# 4_324_039__3_2.net
KiCad netlist of a schematic drawn in Altium Designer
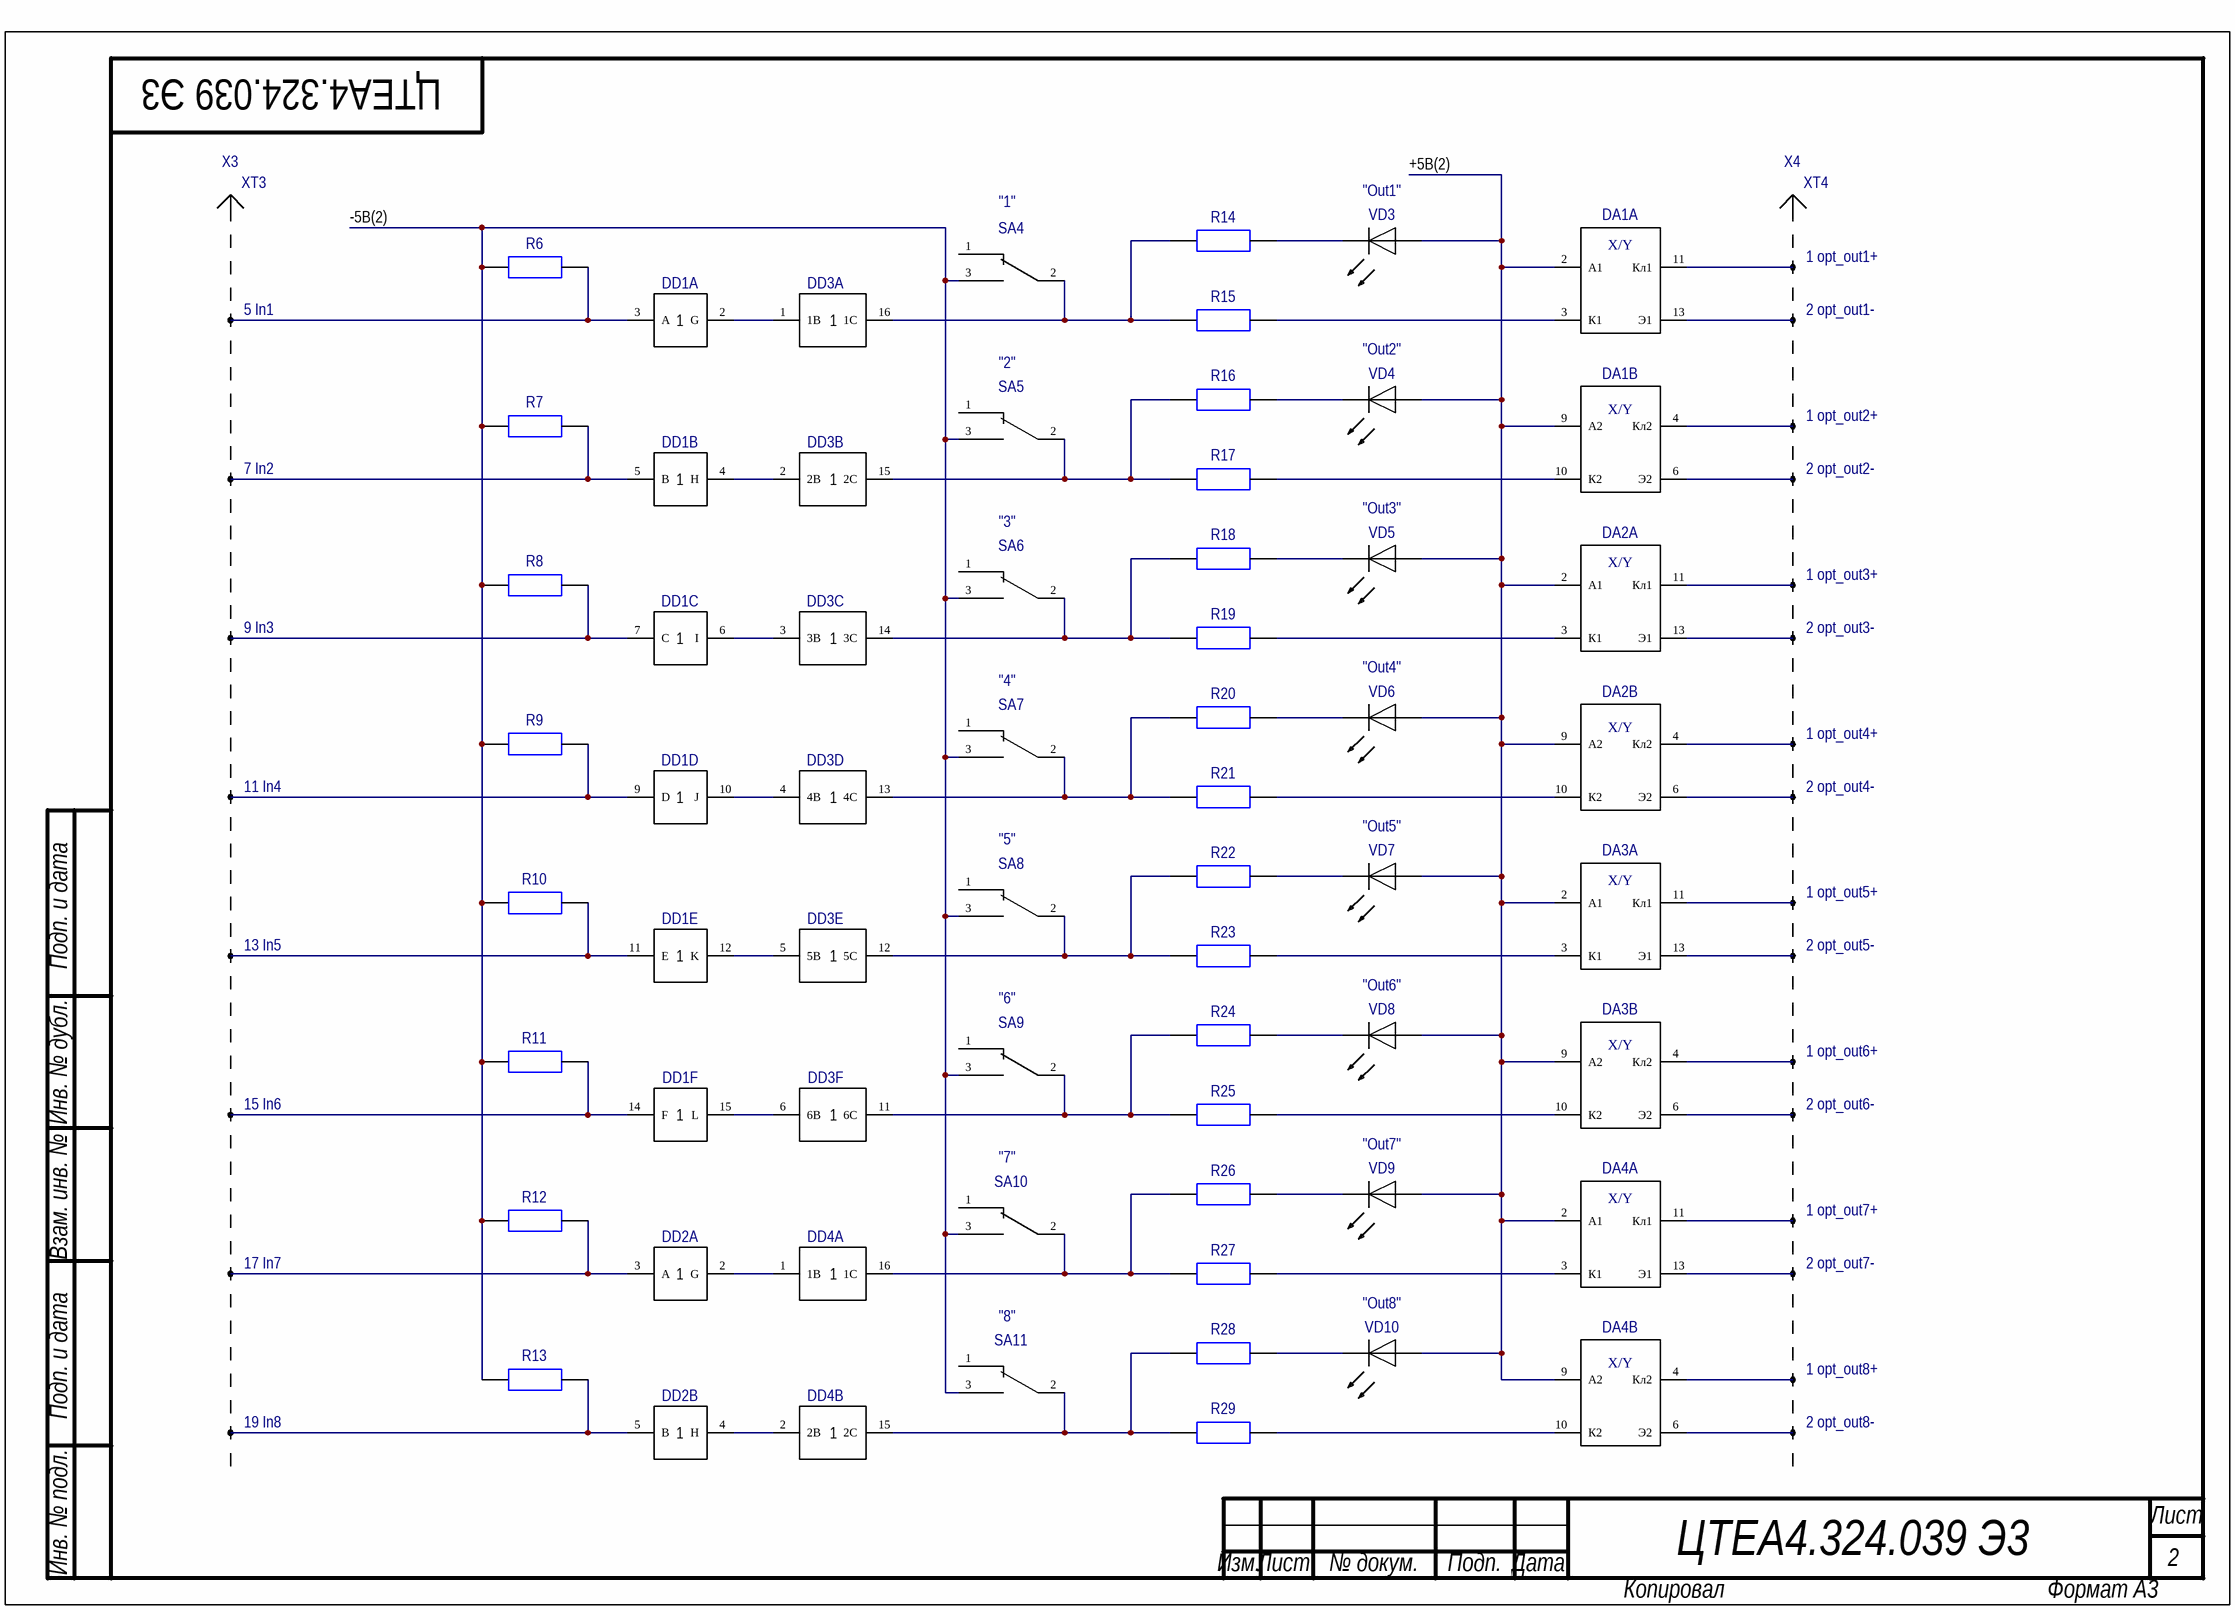
[diagram p0: ЦТЕА4.324.039_Э3_2.SchDoc]

(export (version "E")
  (design (tool "Eeschema 10.0.6"))
  (components
    (comp (ref "DA1")
      (value "249КП1С")
      (footprint "249KP1S_44_3208_125_12-3kl:249KP1S-44_3208_125_12")
      (libsource (lib "249KP1S_44_3208_125_12-3kl") (part "Microshema"))
    )
    (comp (ref "DA2")
      (value "249КП1С")
      (footprint "249KP1S_44_3208_125_12-3kl:249KP1S-44_3208_125_12")
      (libsource (lib "249KP1S_44_3208_125_12-3kl") (part "Microshema"))
    )
    (comp (ref "DA3")
      (value "249КП1С")
      (footprint "249KP1S_44_3208_125_12-3kl:249KP1S-44_3208_125_12")
      (libsource (lib "249KP1S_44_3208_125_12-3kl") (part "Microshema"))
    )
    (comp (ref "DA4")
      (value "249КП1С")
      (footprint "249KP1S_44_3208_125_12-3kl:249KP1S-44_3208_125_12")
      (libsource (lib "249KP1S_44_3208_125_12-3kl") (part "Microshema"))
    )
    (comp (ref "DD1")
      (value "Mikroshema")
      (footprint "CD4050BD")
      (description "CD4050BD")
      (libsource (lib "CD4050BD-3kl") (part "Mikroshema"))
    )
    (comp (ref "DD2")
      (value "Mikroshema")
      (footprint "CD4050BD")
      (description "CD4050BD")
      (libsource (lib "CD4050BD-3kl") (part "Mikroshema"))
    )
    (comp (ref "DD3")
      (value "Mikroshema")
      (footprint "UL2004AD")
      (description "ULN2004")
      (libsource (lib "ULN2004AD-3kl") (part "Mikroshema"))
    )
    (comp (ref "DD4")
      (value "Mikroshema")
      (footprint "UL2004AD")
      (description "ULN2004")
      (libsource (lib "ULN2004AD-3kl") (part "Mikroshema"))
    )
    (comp (ref "R6")
      (value "Res")
      (footprint "CR1206-JW-3301ELF")
      (libsource (lib "CR1206-JW-3301ELF-3kl") (part "Rezistor"))
    )
    (comp (ref "R7")
      (value "Res")
      (footprint "CR1206-JW-3301ELF")
      (libsource (lib "CR1206-JW-3301ELF-3kl") (part "Rezistor"))
    )
    (comp (ref "R8")
      (value "Res")
      (footprint "CR1206-JW-3301ELF")
      (libsource (lib "CR1206-JW-3301ELF-3kl") (part "Rezistor"))
    )
    (comp (ref "R9")
      (value "Res")
      (footprint "CR1206-JW-3301ELF")
      (libsource (lib "CR1206-JW-3301ELF-3kl") (part "Rezistor"))
    )
    (comp (ref "R10")
      (value "Res")
      (footprint "CR1206-JW-3301ELF")
      (libsource (lib "CR1206-JW-3301ELF-3kl") (part "Rezistor"))
    )
    (comp (ref "R11")
      (value "Res")
      (footprint "CR1206-JW-3301ELF")
      (libsource (lib "CR1206-JW-3301ELF-3kl") (part "Rezistor"))
    )
    (comp (ref "R12")
      (value "Res")
      (footprint "CR1206-JW-3301ELF")
      (libsource (lib "CR1206-JW-3301ELF-3kl") (part "Rezistor"))
    )
    (comp (ref "R13")
      (value "Res")
      (footprint "CR1206-JW-3301ELF")
      (libsource (lib "CR1206-JW-3301ELF-3kl") (part "Rezistor"))
    )
    (comp (ref "R14")
      (value "Res")
      (footprint "CR1206-JW-4700ELF")
      (libsource (lib "CR1206-JW-4700ELF-3kl") (part "Rezistor"))
    )
    (comp (ref "R15")
      (value "Res")
      (footprint "CR1206-JW-3300ELF")
      (libsource (lib "CR1206-JW-3300ELF-3kl") (part "Rezistor"))
    )
    (comp (ref "R16")
      (value "Res")
      (footprint "CR1206-JW-4700ELF")
      (libsource (lib "CR1206-JW-4700ELF-3kl") (part "Rezistor"))
    )
    (comp (ref "R17")
      (value "Res")
      (footprint "CR1206-JW-3300ELF")
      (libsource (lib "CR1206-JW-3300ELF-3kl") (part "Rezistor"))
    )
    (comp (ref "R18")
      (value "Res")
      (footprint "CR1206-JW-4700ELF")
      (libsource (lib "CR1206-JW-4700ELF-3kl") (part "Rezistor"))
    )
    (comp (ref "R19")
      (value "Res")
      (footprint "CR1206-JW-3300ELF")
      (libsource (lib "CR1206-JW-3300ELF-3kl") (part "Rezistor"))
    )
    (comp (ref "R20")
      (value "Res")
      (footprint "CR1206-JW-4700ELF")
      (libsource (lib "CR1206-JW-4700ELF-3kl") (part "Rezistor"))
    )
    (comp (ref "R21")
      (value "Res")
      (footprint "CR1206-JW-3300ELF")
      (libsource (lib "CR1206-JW-3300ELF-3kl") (part "Rezistor"))
    )
    (comp (ref "R22")
      (value "Res")
      (footprint "CR1206-JW-4700ELF")
      (libsource (lib "CR1206-JW-4700ELF-3kl") (part "Rezistor"))
    )
    (comp (ref "R23")
      (value "Res")
      (footprint "CR1206-JW-3300ELF")
      (libsource (lib "CR1206-JW-3300ELF-3kl") (part "Rezistor"))
    )
    (comp (ref "R24")
      (value "Res")
      (footprint "CR1206-JW-4700ELF")
      (libsource (lib "CR1206-JW-4700ELF-3kl") (part "Rezistor"))
    )
    (comp (ref "R25")
      (value "Res")
      (footprint "CR1206-JW-3300ELF")
      (libsource (lib "CR1206-JW-3300ELF-3kl") (part "Rezistor"))
    )
    (comp (ref "R26")
      (value "Res")
      (footprint "CR1206-JW-4700ELF")
      (libsource (lib "CR1206-JW-4700ELF-3kl") (part "Rezistor"))
    )
    (comp (ref "R27")
      (value "Res")
      (footprint "CR1206-JW-3300ELF")
      (libsource (lib "CR1206-JW-3300ELF-3kl") (part "Rezistor"))
    )
    (comp (ref "R28")
      (value "Res")
      (footprint "CR1206-JW-4700ELF")
      (libsource (lib "CR1206-JW-4700ELF-3kl") (part "Rezistor"))
    )
    (comp (ref "R29")
      (value "Res")
      (footprint "CR1206-JW-3300ELF")
      (libsource (lib "CR1206-JW-3300ELF-3kl") (part "Rezistor"))
    )
    (comp (ref "SA4")
      (value "\"1\"")
      (footprint "7101SYZQE-3kl:7107SYZQE")
      (libsource (lib "7101SYZQE-3kl") (part "Perekljuchatel"))
    )
    (comp (ref "SA5")
      (value "\"2\"")
      (footprint "7101SYZQE-3kl:7107SYZQE")
      (libsource (lib "7101SYZQE-3kl") (part "Perekljuchatel"))
    )
    (comp (ref "SA6")
      (value "\"3\"")
      (footprint "7101SYZQE-3kl:7107SYZQE")
      (libsource (lib "7101SYZQE-3kl") (part "Perekljuchatel"))
    )
    (comp (ref "SA7")
      (value "\"4\"")
      (footprint "7101SYZQE-3kl:7107SYZQE")
      (libsource (lib "7101SYZQE-3kl") (part "Perekljuchatel"))
    )
    (comp (ref "SA8")
      (value "\"5\"")
      (footprint "7101SYZQE-3kl:7107SYZQE")
      (libsource (lib "7101SYZQE-3kl") (part "Perekljuchatel"))
    )
    (comp (ref "SA9")
      (value "\"6\"")
      (footprint "7101SYZQE-3kl:7107SYZQE")
      (libsource (lib "7101SYZQE-3kl") (part "Perekljuchatel"))
    )
    (comp (ref "SA10")
      (value "\"7\"")
      (footprint "7101SYZQE-3kl:7107SYZQE")
      (libsource (lib "7101SYZQE-3kl") (part "Perekljuchatel"))
    )
    (comp (ref "SA11")
      (value "\"8\"")
      (footprint "7101SYZQE-3kl:7107SYZQE")
      (libsource (lib "7101SYZQE-3kl") (part "Perekljuchatel"))
    )
    (comp (ref "VD3")
      (value "\"Out1\"")
      (footprint "HLMP-D150")
      (libsource (lib "HLMP-D150-3kl") (part "Svetodiod"))
    )
    (comp (ref "VD4")
      (value "\"Out2\"")
      (footprint "HLMP-D150")
      (libsource (lib "HLMP-D150-3kl") (part "Svetodiod"))
    )
    (comp (ref "VD5")
      (value "\"Out3\"")
      (footprint "HLMP-D150")
      (libsource (lib "HLMP-D150-3kl") (part "Svetodiod"))
    )
    (comp (ref "VD6")
      (value "\"Out4\"")
      (footprint "HLMP-D150")
      (libsource (lib "HLMP-D150-3kl") (part "Svetodiod"))
    )
    (comp (ref "VD7")
      (value "\"Out5\"")
      (footprint "HLMP-D150")
      (libsource (lib "HLMP-D150-3kl") (part "Svetodiod"))
    )
    (comp (ref "VD8")
      (value "\"Out6\"")
      (footprint "HLMP-D150")
      (libsource (lib "HLMP-D150-3kl") (part "Svetodiod"))
    )
    (comp (ref "VD9")
      (value "\"Out7\"")
      (footprint "HLMP-D150")
      (libsource (lib "HLMP-D150-3kl") (part "Svetodiod"))
    )
    (comp (ref "VD10")
      (value "\"Out8\"")
      (footprint "HLMP-D150")
      (libsource (lib "HLMP-D150-3kl") (part "Svetodiod"))
    )
    (comp (ref "XT3")
      (value "5 In1")
      (footprint "PLD-40")
      (libsource (lib "PLD-40-3kl") (part "Razem shtyrevoj"))
    )
    (comp (ref "XT4")
      (value "1 opt_out1+")
      (footprint "PLD-18")
      (libsource (lib "PLD-18-3kl") (part "Razem shtyrevoj"))
    )
  )
  (nets
    (net (code "1") (name "/+5V") (class "Default")
      (node (ref "DA1") (pin "2") (pinfunction "А1_2") (pintype "passive"))
      (node (ref "DA1") (pin "9") (pinfunction "А2_9") (pintype "passive"))
      (node (ref "DA2") (pin "2") (pinfunction "А1_2") (pintype "passive"))
      (node (ref "DA2") (pin "9") (pinfunction "А2_9") (pintype "passive"))
      (node (ref "DA3") (pin "2") (pinfunction "А1_2") (pintype "passive"))
      (node (ref "DA3") (pin "9") (pinfunction "А2_9") (pintype "passive"))
      (node (ref "DA4") (pin "2") (pinfunction "А1_2") (pintype "passive"))
      (node (ref "DA4") (pin "9") (pinfunction "А2_9") (pintype "passive"))
      (node (ref "VD10") (pin "1") (pinfunction "A_1") (pintype "passive"))
      (node (ref "VD3") (pin "1") (pinfunction "A_1") (pintype "passive"))
      (node (ref "VD4") (pin "1") (pinfunction "A_1") (pintype "passive"))
      (node (ref "VD5") (pin "1") (pinfunction "A_1") (pintype "passive"))
      (node (ref "VD6") (pin "1") (pinfunction "A_1") (pintype "passive"))
      (node (ref "VD7") (pin "1") (pinfunction "A_1") (pintype "passive"))
      (node (ref "VD8") (pin "1") (pinfunction "A_1") (pintype "passive"))
      (node (ref "VD9") (pin "1") (pinfunction "A_1") (pintype "passive"))
    )
    (net (code "2") (name "/GND") (class "Default")
      (node (ref "R10") (pin "1") (pinfunction "1_1") (pintype "passive"))
      (node (ref "R11") (pin "1") (pinfunction "1_1") (pintype "passive"))
      (node (ref "R12") (pin "1") (pinfunction "1_1") (pintype "passive"))
      (node (ref "R13") (pin "1") (pinfunction "1_1") (pintype "passive"))
      (node (ref "R6") (pin "1") (pinfunction "1_1") (pintype "passive"))
      (node (ref "R7") (pin "1") (pinfunction "1_1") (pintype "passive"))
      (node (ref "R8") (pin "1") (pinfunction "1_1") (pintype "passive"))
      (node (ref "R9") (pin "1") (pinfunction "1_1") (pintype "passive"))
      (node (ref "SA10") (pin "3") (pinfunction "3_3") (pintype "passive"))
      (node (ref "SA11") (pin "3") (pinfunction "3_3") (pintype "passive"))
      (node (ref "SA4") (pin "3") (pinfunction "3_3") (pintype "passive"))
      (node (ref "SA5") (pin "3") (pinfunction "3_3") (pintype "passive"))
      (node (ref "SA6") (pin "3") (pinfunction "3_3") (pintype "passive"))
      (node (ref "SA7") (pin "3") (pinfunction "3_3") (pintype "passive"))
      (node (ref "SA8") (pin "3") (pinfunction "3_3") (pintype "passive"))
      (node (ref "SA9") (pin "3") (pinfunction "3_3") (pintype "passive"))
    )
    (net (code "3") (name "Net-(DA1A-К1)") (class "Default")
      (node (ref "DA1") (pin "3") (pinfunction "К1_3") (pintype "passive"))
      (node (ref "R15") (pin "2") (pinfunction "2_2") (pintype "passive"))
    )
    (net (code "4") (name "Net-(DA1A-Кл1)") (class "Default")
      (node (ref "DA1") (pin "11") (pinfunction "Кл1_11") (pintype "passive"))
      (node (ref "XT4") (pin "1") (pinfunction "1_1") (pintype "passive"))
    )
    (net (code "5") (name "Net-(DA1A-Э1)") (class "Default")
      (node (ref "DA1") (pin "13") (pinfunction "Э1_13") (pintype "passive"))
      (node (ref "XT4") (pin "2") (pinfunction "2_2") (pintype "passive"))
    )
    (net (code "6") (name "Net-(DA1B-К2)") (class "Default")
      (node (ref "DA1") (pin "10") (pinfunction "К2_10") (pintype "passive"))
      (node (ref "R17") (pin "2") (pinfunction "2_2") (pintype "passive"))
    )
    (net (code "7") (name "Net-(DA1B-Кл2)") (class "Default")
      (node (ref "DA1") (pin "4") (pinfunction "Кл2_4") (pintype "passive"))
      (node (ref "XT4") (pin "3") (pinfunction "3_3") (pintype "passive"))
    )
    (net (code "8") (name "Net-(DA1B-Э2)") (class "Default")
      (node (ref "DA1") (pin "6") (pinfunction "Э2_6") (pintype "passive"))
      (node (ref "XT4") (pin "4") (pinfunction "4_4") (pintype "passive"))
    )
    (net (code "9") (name "Net-(DA2A-К1)") (class "Default")
      (node (ref "DA2") (pin "3") (pinfunction "К1_3") (pintype "passive"))
      (node (ref "R19") (pin "2") (pinfunction "2_2") (pintype "passive"))
    )
    (net (code "10") (name "Net-(DA2A-Кл1)") (class "Default")
      (node (ref "DA2") (pin "11") (pinfunction "Кл1_11") (pintype "passive"))
      (node (ref "XT4") (pin "5") (pinfunction "5_5") (pintype "passive"))
    )
    (net (code "11") (name "Net-(DA2A-Э1)") (class "Default")
      (node (ref "DA2") (pin "13") (pinfunction "Э1_13") (pintype "passive"))
      (node (ref "XT4") (pin "6") (pinfunction "6_6") (pintype "passive"))
    )
    (net (code "12") (name "Net-(DA2B-К2)") (class "Default")
      (node (ref "DA2") (pin "10") (pinfunction "К2_10") (pintype "passive"))
      (node (ref "R21") (pin "2") (pinfunction "2_2") (pintype "passive"))
    )
    (net (code "13") (name "Net-(DA2B-Кл2)") (class "Default")
      (node (ref "DA2") (pin "4") (pinfunction "Кл2_4") (pintype "passive"))
      (node (ref "XT4") (pin "7") (pinfunction "7_7") (pintype "passive"))
    )
    (net (code "14") (name "Net-(DA2B-Э2)") (class "Default")
      (node (ref "DA2") (pin "6") (pinfunction "Э2_6") (pintype "passive"))
      (node (ref "XT4") (pin "8") (pinfunction "8_8") (pintype "passive"))
    )
    (net (code "15") (name "Net-(DA3A-К1)") (class "Default")
      (node (ref "DA3") (pin "3") (pinfunction "К1_3") (pintype "passive"))
      (node (ref "R23") (pin "2") (pinfunction "2_2") (pintype "passive"))
    )
    (net (code "16") (name "Net-(DA3A-Кл1)") (class "Default")
      (node (ref "DA3") (pin "11") (pinfunction "Кл1_11") (pintype "passive"))
      (node (ref "XT4") (pin "9") (pinfunction "9_9") (pintype "passive"))
    )
    (net (code "17") (name "Net-(DA3A-Э1)") (class "Default")
      (node (ref "DA3") (pin "13") (pinfunction "Э1_13") (pintype "passive"))
      (node (ref "XT4") (pin "10") (pinfunction "10_10") (pintype "passive"))
    )
    (net (code "18") (name "Net-(DA3B-К2)") (class "Default")
      (node (ref "DA3") (pin "10") (pinfunction "К2_10") (pintype "passive"))
      (node (ref "R25") (pin "2") (pinfunction "2_2") (pintype "passive"))
    )
    (net (code "19") (name "Net-(DA3B-Кл2)") (class "Default")
      (node (ref "DA3") (pin "4") (pinfunction "Кл2_4") (pintype "passive"))
      (node (ref "XT4") (pin "11") (pinfunction "11_11") (pintype "passive"))
    )
    (net (code "20") (name "Net-(DA3B-Э2)") (class "Default")
      (node (ref "DA3") (pin "6") (pinfunction "Э2_6") (pintype "passive"))
      (node (ref "XT4") (pin "12") (pinfunction "12_12") (pintype "passive"))
    )
    (net (code "21") (name "Net-(DA4A-К1)") (class "Default")
      (node (ref "DA4") (pin "3") (pinfunction "К1_3") (pintype "passive"))
      (node (ref "R27") (pin "2") (pinfunction "2_2") (pintype "passive"))
    )
    (net (code "22") (name "Net-(DA4A-Кл1)") (class "Default")
      (node (ref "DA4") (pin "11") (pinfunction "Кл1_11") (pintype "passive"))
      (node (ref "XT4") (pin "13") (pinfunction "13_13") (pintype "passive"))
    )
    (net (code "23") (name "Net-(DA4A-Э1)") (class "Default")
      (node (ref "DA4") (pin "13") (pinfunction "Э1_13") (pintype "passive"))
      (node (ref "XT4") (pin "14") (pinfunction "14_14") (pintype "passive"))
    )
    (net (code "24") (name "Net-(DA4B-К2)") (class "Default")
      (node (ref "DA4") (pin "10") (pinfunction "К2_10") (pintype "passive"))
      (node (ref "R29") (pin "2") (pinfunction "2_2") (pintype "passive"))
    )
    (net (code "25") (name "Net-(DA4B-Кл2)") (class "Default")
      (node (ref "DA4") (pin "4") (pinfunction "Кл2_4") (pintype "passive"))
      (node (ref "XT4") (pin "15") (pinfunction "15_15") (pintype "passive"))
    )
    (net (code "26") (name "Net-(DA4B-Э2)") (class "Default")
      (node (ref "DA4") (pin "6") (pinfunction "Э2_6") (pintype "passive"))
      (node (ref "XT4") (pin "16") (pinfunction "16_16") (pintype "passive"))
    )
    (net (code "27") (name "Net-(DD1A-A)") (class "Default")
      (node (ref "DD1") (pin "3") (pinfunction "A_3") (pintype "passive"))
      (node (ref "R6") (pin "2") (pinfunction "2_2") (pintype "passive"))
      (node (ref "XT3") (pin "5") (pinfunction "5_5") (pintype "passive"))
    )
    (net (code "28") (name "Net-(DD1A-G)") (class "Default")
      (node (ref "DD1") (pin "2") (pinfunction "G_2") (pintype "passive"))
      (node (ref "DD3") (pin "1") (pinfunction "1B_1") (pintype "passive"))
    )
    (net (code "29") (name "Net-(DD1B-B)") (class "Default")
      (node (ref "DD1") (pin "5") (pinfunction "B_5") (pintype "passive"))
      (node (ref "R7") (pin "2") (pinfunction "2_2") (pintype "passive"))
      (node (ref "XT3") (pin "7") (pinfunction "7_7") (pintype "passive"))
    )
    (net (code "30") (name "Net-(DD1B-H)") (class "Default")
      (node (ref "DD1") (pin "4") (pinfunction "H_4") (pintype "passive"))
      (node (ref "DD3") (pin "2") (pinfunction "2B_2") (pintype "passive"))
    )
    (net (code "31") (name "Net-(DD1C-C)") (class "Default")
      (node (ref "DD1") (pin "7") (pinfunction "C_7") (pintype "passive"))
      (node (ref "R8") (pin "2") (pinfunction "2_2") (pintype "passive"))
      (node (ref "XT3") (pin "9") (pinfunction "9_9") (pintype "passive"))
    )
    (net (code "32") (name "Net-(DD1C-I)") (class "Default")
      (node (ref "DD1") (pin "6") (pinfunction "I_6") (pintype "passive"))
      (node (ref "DD3") (pin "3") (pinfunction "3B_3") (pintype "passive"))
    )
    (net (code "33") (name "Net-(DD1D-D)") (class "Default")
      (node (ref "DD1") (pin "9") (pinfunction "D_9") (pintype "passive"))
      (node (ref "R9") (pin "2") (pinfunction "2_2") (pintype "passive"))
      (node (ref "XT3") (pin "11") (pinfunction "11_11") (pintype "passive"))
    )
    (net (code "34") (name "Net-(DD1D-J)") (class "Default")
      (node (ref "DD1") (pin "10") (pinfunction "J_10") (pintype "passive"))
      (node (ref "DD3") (pin "4") (pinfunction "4B_4") (pintype "passive"))
    )
    (net (code "35") (name "Net-(DD1E-E)") (class "Default")
      (node (ref "DD1") (pin "11") (pinfunction "E_11") (pintype "passive"))
      (node (ref "R10") (pin "2") (pinfunction "2_2") (pintype "passive"))
      (node (ref "XT3") (pin "13") (pinfunction "13_13") (pintype "passive"))
    )
    (net (code "36") (name "Net-(DD1E-K)") (class "Default")
      (node (ref "DD1") (pin "12") (pinfunction "K_12") (pintype "passive"))
      (node (ref "DD3") (pin "5") (pinfunction "5B_5") (pintype "passive"))
    )
    (net (code "37") (name "Net-(DD1F-F)") (class "Default")
      (node (ref "DD1") (pin "14") (pinfunction "F_14") (pintype "passive"))
      (node (ref "R11") (pin "2") (pinfunction "2_2") (pintype "passive"))
      (node (ref "XT3") (pin "15") (pinfunction "15_15") (pintype "passive"))
    )
    (net (code "38") (name "Net-(DD1F-L)") (class "Default")
      (node (ref "DD1") (pin "15") (pinfunction "L_15") (pintype "passive"))
      (node (ref "DD3") (pin "6") (pinfunction "6B_6") (pintype "passive"))
    )
    (net (code "39") (name "Net-(DD2A-A)") (class "Default")
      (node (ref "DD2") (pin "3") (pinfunction "A_3") (pintype "passive"))
      (node (ref "R12") (pin "2") (pinfunction "2_2") (pintype "passive"))
      (node (ref "XT3") (pin "17") (pinfunction "17_17") (pintype "passive"))
    )
    (net (code "40") (name "Net-(DD2A-G)") (class "Default")
      (node (ref "DD2") (pin "2") (pinfunction "G_2") (pintype "passive"))
      (node (ref "DD4") (pin "1") (pinfunction "1B_1") (pintype "passive"))
    )
    (net (code "41") (name "Net-(DD2B-B)") (class "Default")
      (node (ref "DD2") (pin "5") (pinfunction "B_5") (pintype "passive"))
      (node (ref "R13") (pin "2") (pinfunction "2_2") (pintype "passive"))
      (node (ref "XT3") (pin "19") (pinfunction "19_19") (pintype "passive"))
    )
    (net (code "42") (name "Net-(DD2B-H)") (class "Default")
      (node (ref "DD2") (pin "4") (pinfunction "H_4") (pintype "passive"))
      (node (ref "DD4") (pin "2") (pinfunction "2B_2") (pintype "passive"))
    )
    (net (code "43") (name "Net-(DD3A-1C)") (class "Default")
      (node (ref "DD3") (pin "16") (pinfunction "1C_16") (pintype "passive"))
      (node (ref "R14") (pin "1") (pinfunction "1_1") (pintype "passive"))
      (node (ref "R15") (pin "1") (pinfunction "1_1") (pintype "passive"))
      (node (ref "SA4") (pin "2") (pinfunction "2_2") (pintype "passive"))
    )
    (net (code "44") (name "Net-(DD3B-2C)") (class "Default")
      (node (ref "DD3") (pin "15") (pinfunction "2C_15") (pintype "passive"))
      (node (ref "R16") (pin "1") (pinfunction "1_1") (pintype "passive"))
      (node (ref "R17") (pin "1") (pinfunction "1_1") (pintype "passive"))
      (node (ref "SA5") (pin "2") (pinfunction "2_2") (pintype "passive"))
    )
    (net (code "45") (name "Net-(DD3C-3C)") (class "Default")
      (node (ref "DD3") (pin "14") (pinfunction "3C_14") (pintype "passive"))
      (node (ref "R18") (pin "1") (pinfunction "1_1") (pintype "passive"))
      (node (ref "R19") (pin "1") (pinfunction "1_1") (pintype "passive"))
      (node (ref "SA6") (pin "2") (pinfunction "2_2") (pintype "passive"))
    )
    (net (code "46") (name "Net-(DD3D-4C)") (class "Default")
      (node (ref "DD3") (pin "13") (pinfunction "4C_13") (pintype "passive"))
      (node (ref "R20") (pin "1") (pinfunction "1_1") (pintype "passive"))
      (node (ref "R21") (pin "1") (pinfunction "1_1") (pintype "passive"))
      (node (ref "SA7") (pin "2") (pinfunction "2_2") (pintype "passive"))
    )
    (net (code "47") (name "Net-(DD3E-5C)") (class "Default")
      (node (ref "DD3") (pin "12") (pinfunction "5C_12") (pintype "passive"))
      (node (ref "R22") (pin "1") (pinfunction "1_1") (pintype "passive"))
      (node (ref "R23") (pin "1") (pinfunction "1_1") (pintype "passive"))
      (node (ref "SA8") (pin "2") (pinfunction "2_2") (pintype "passive"))
    )
    (net (code "48") (name "Net-(DD3F-6C)") (class "Default")
      (node (ref "DD3") (pin "11") (pinfunction "6C_11") (pintype "passive"))
      (node (ref "R24") (pin "1") (pinfunction "1_1") (pintype "passive"))
      (node (ref "R25") (pin "1") (pinfunction "1_1") (pintype "passive"))
      (node (ref "SA9") (pin "2") (pinfunction "2_2") (pintype "passive"))
    )
    (net (code "49") (name "Net-(DD4A-1C)") (class "Default")
      (node (ref "DD4") (pin "16") (pinfunction "1C_16") (pintype "passive"))
      (node (ref "R26") (pin "1") (pinfunction "1_1") (pintype "passive"))
      (node (ref "R27") (pin "1") (pinfunction "1_1") (pintype "passive"))
      (node (ref "SA10") (pin "2") (pinfunction "2_2") (pintype "passive"))
    )
    (net (code "50") (name "Net-(DD4B-2C)") (class "Default")
      (node (ref "DD4") (pin "15") (pinfunction "2C_15") (pintype "passive"))
      (node (ref "R28") (pin "1") (pinfunction "1_1") (pintype "passive"))
      (node (ref "R29") (pin "1") (pinfunction "1_1") (pintype "passive"))
      (node (ref "SA11") (pin "2") (pinfunction "2_2") (pintype "passive"))
    )
    (net (code "51") (name "Net-(VD3-C)") (class "Default")
      (node (ref "R14") (pin "2") (pinfunction "2_2") (pintype "passive"))
      (node (ref "VD3") (pin "2") (pinfunction "C_2") (pintype "passive"))
    )
    (net (code "52") (name "Net-(VD4-C)") (class "Default")
      (node (ref "R16") (pin "2") (pinfunction "2_2") (pintype "passive"))
      (node (ref "VD4") (pin "2") (pinfunction "C_2") (pintype "passive"))
    )
    (net (code "53") (name "Net-(VD5-C)") (class "Default")
      (node (ref "R18") (pin "2") (pinfunction "2_2") (pintype "passive"))
      (node (ref "VD5") (pin "2") (pinfunction "C_2") (pintype "passive"))
    )
    (net (code "54") (name "Net-(VD6-C)") (class "Default")
      (node (ref "R20") (pin "2") (pinfunction "2_2") (pintype "passive"))
      (node (ref "VD6") (pin "2") (pinfunction "C_2") (pintype "passive"))
    )
    (net (code "55") (name "Net-(VD7-C)") (class "Default")
      (node (ref "R22") (pin "2") (pinfunction "2_2") (pintype "passive"))
      (node (ref "VD7") (pin "2") (pinfunction "C_2") (pintype "passive"))
    )
    (net (code "56") (name "Net-(VD8-C)") (class "Default")
      (node (ref "R24") (pin "2") (pinfunction "2_2") (pintype "passive"))
      (node (ref "VD8") (pin "2") (pinfunction "C_2") (pintype "passive"))
    )
    (net (code "57") (name "Net-(VD9-C)") (class "Default")
      (node (ref "R26") (pin "2") (pinfunction "2_2") (pintype "passive"))
      (node (ref "VD9") (pin "2") (pinfunction "C_2") (pintype "passive"))
    )
    (net (code "58") (name "Net-(VD10-C)") (class "Default")
      (node (ref "R28") (pin "2") (pinfunction "2_2") (pintype "passive"))
      (node (ref "VD10") (pin "2") (pinfunction "C_2") (pintype "passive"))
    )
    (net (code "59") (name "unconnected-(SA4-Pad1)") (class "Default")
      (node (ref "SA4") (pin "1") (pinfunction "1_1") (pintype "passive"))
    )
    (net (code "60") (name "unconnected-(SA5-Pad1)") (class "Default")
      (node (ref "SA5") (pin "1") (pinfunction "1_1") (pintype "passive"))
    )
    (net (code "61") (name "unconnected-(SA6-Pad1)") (class "Default")
      (node (ref "SA6") (pin "1") (pinfunction "1_1") (pintype "passive"))
    )
    (net (code "62") (name "unconnected-(SA7-Pad1)") (class "Default")
      (node (ref "SA7") (pin "1") (pinfunction "1_1") (pintype "passive"))
    )
    (net (code "63") (name "unconnected-(SA8-Pad1)") (class "Default")
      (node (ref "SA8") (pin "1") (pinfunction "1_1") (pintype "passive"))
    )
    (net (code "64") (name "unconnected-(SA9-Pad1)") (class "Default")
      (node (ref "SA9") (pin "1") (pinfunction "1_1") (pintype "passive"))
    )
    (net (code "65") (name "unconnected-(SA10-Pad1)") (class "Default")
      (node (ref "SA10") (pin "1") (pinfunction "1_1") (pintype "passive"))
    )
    (net (code "66") (name "unconnected-(SA11-Pad1)") (class "Default")
      (node (ref "SA11") (pin "1") (pinfunction "1_1") (pintype "passive"))
    )
  )
)
